# VM-MCU_v4_5.net
KiCad netlist of a schematic drawn in EAGLE
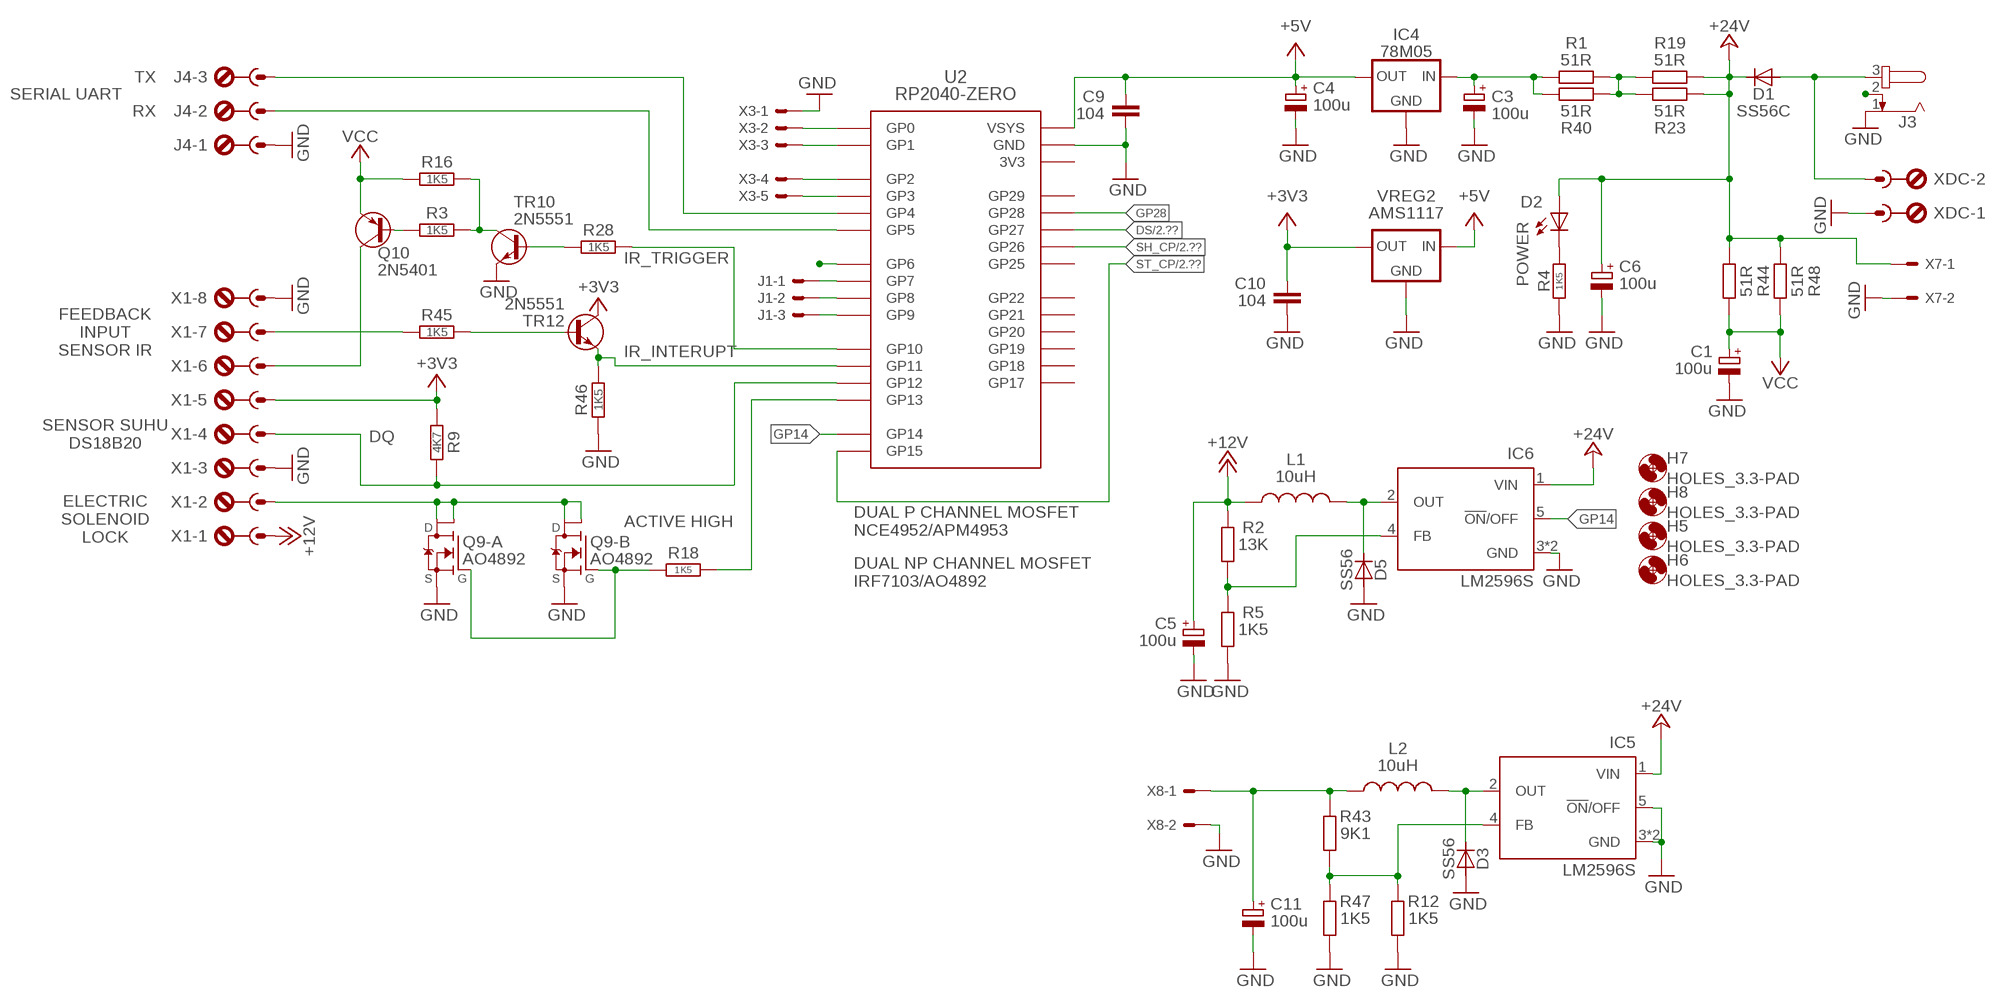
[diagram p0: schematic, sheet 1]
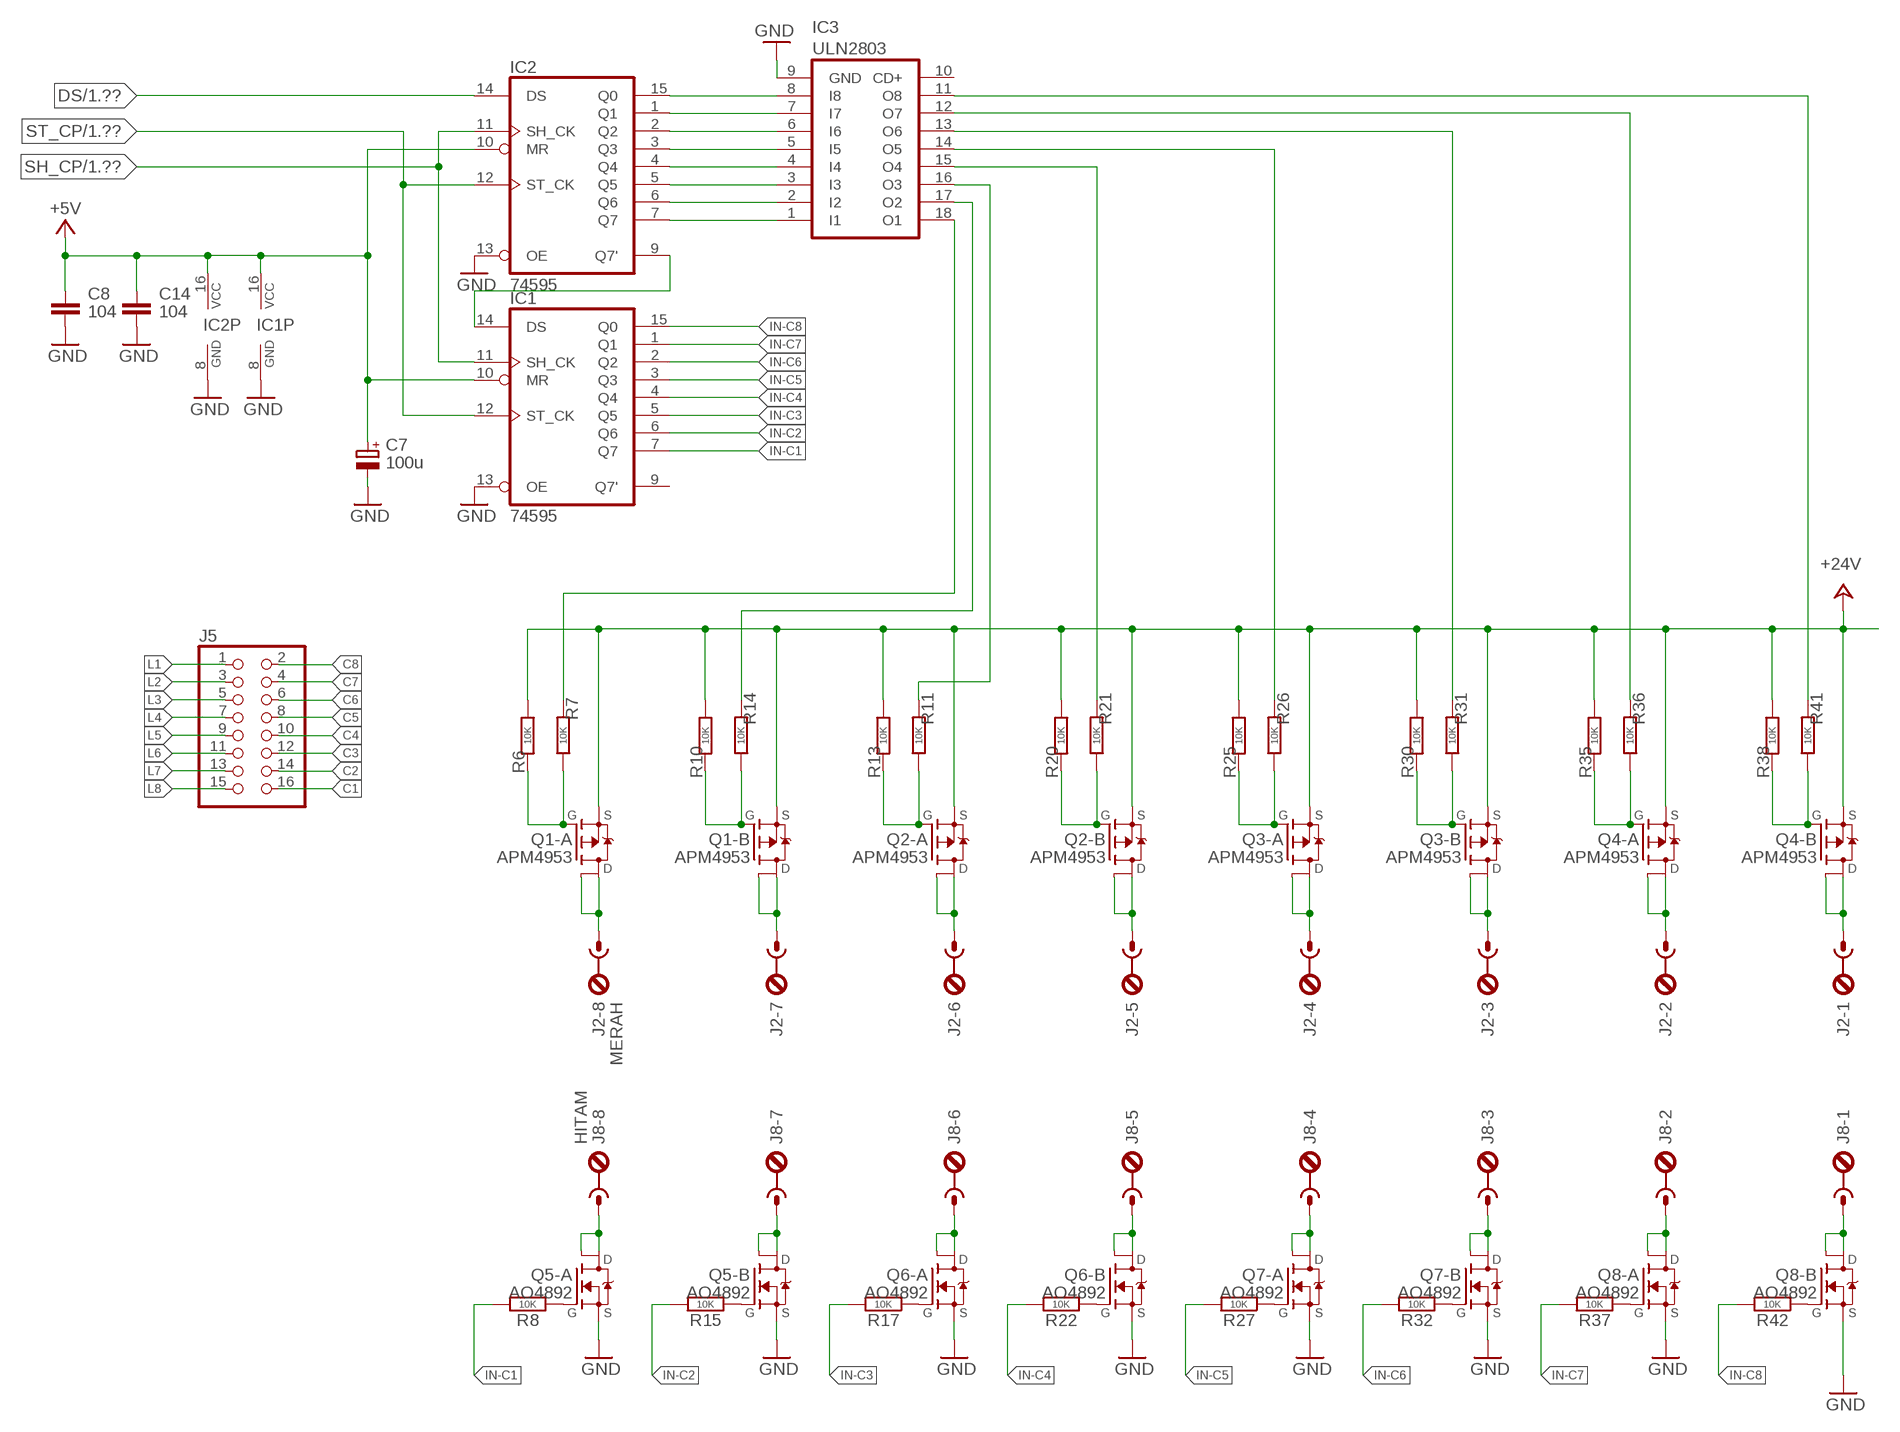
[diagram p1: schematic, sheet 2]

(export (version "E")
  (design (tool "Eeschema 10.0.6"))
  (components
    (comp (ref "C7")
      (value "100u")
      (footprint "eagle-import:UD-6,3X7,7_NICHICON")
      (libsource (lib "eagle-import") (part "ELCO_UD-6,3X7,7"))
    )
    (comp (ref "C8")
      (value "104")
      (footprint "eagle-import:C1206")
      (libsource (lib "eagle-import") (part "CAP_SMD-C1206"))
    )
    (comp (ref "C14")
      (value "104")
      (footprint "eagle-import:C1206")
      (libsource (lib "eagle-import") (part "CAP_SMD-C1206"))
    )
    (comp (ref "IC1")
      (value "74595")
      (footprint "eagle-import:SO16")
      (libsource (lib "eagle-import") (part "74595"))
    )
    (comp (ref "IC2")
      (value "74595")
      (footprint "eagle-import:SO16")
      (libsource (lib "eagle-import") (part "74595"))
    )
    (comp (ref "IC3")
      (value "ULN2803")
      (footprint "eagle-import:SO18W")
      (libsource (lib "eagle-import") (part "ULN2805ASO18"))
    )
    (comp (ref "J2")
      (value "MERAH")
      (footprint "eagle-import:KF2EDG-3.81_8P")
      (libsource (lib "eagle-import") (part "TBLOCK-8P_KF2EDG-3.81"))
    )
    (comp (ref "J5")
      (value "PINHEAD_2X8SMT")
      (footprint "eagle-import:PINHEAD-SMT_2X08")
      (libsource (lib "eagle-import") (part "PINHEAD_2X8SMT"))
    )
    (comp (ref "J8")
      (value "HITAM")
      (footprint "eagle-import:KF2EDG-3.81_8P")
      (libsource (lib "eagle-import") (part "TBLOCK-8P_KF2EDG-3.81"))
    )
    (comp (ref "Q1")
      (value "APM4953")
      (footprint "eagle-import:SO-8")
      (libsource (lib "eagle-import") (part "DUALFET-P_P+PNCE4953"))
    )
    (comp (ref "Q2")
      (value "APM4953")
      (footprint "eagle-import:SO-8")
      (libsource (lib "eagle-import") (part "DUALFET-P_P+PNCE4953"))
    )
    (comp (ref "Q3")
      (value "APM4953")
      (footprint "eagle-import:SO-8")
      (libsource (lib "eagle-import") (part "DUALFET-P_P+PNCE4953"))
    )
    (comp (ref "Q4")
      (value "APM4953")
      (footprint "eagle-import:SO-8")
      (libsource (lib "eagle-import") (part "DUALFET-P_P+PNCE4953"))
    )
    (comp (ref "Q5")
      (value "AO4892")
      (footprint "eagle-import:SO-8")
      (libsource (lib "eagle-import") (part "DUALFET-N_N+NAO4892"))
    )
    (comp (ref "Q6")
      (value "AO4892")
      (footprint "eagle-import:SO-8")
      (libsource (lib "eagle-import") (part "DUALFET-N_N+NAO4892"))
    )
    (comp (ref "Q7")
      (value "AO4892")
      (footprint "eagle-import:SO-8")
      (libsource (lib "eagle-import") (part "DUALFET-N_N+NAO4892"))
    )
    (comp (ref "Q8")
      (value "AO4892")
      (footprint "eagle-import:SO-8")
      (libsource (lib "eagle-import") (part "DUALFET-N_N+NAO4892"))
    )
    (comp (ref "R6")
      (value "10K")
      (footprint "eagle-import:R1206")
      (libsource (lib "eagle-import") (part "RESISTOR_1206"))
    )
    (comp (ref "R7")
      (value "10K")
      (footprint "eagle-import:R1206")
      (libsource (lib "eagle-import") (part "RESISTOR_1206"))
    )
    (comp (ref "R8")
      (value "10K")
      (footprint "eagle-import:R1206")
      (libsource (lib "eagle-import") (part "RESISTOR_1206"))
    )
    (comp (ref "R10")
      (value "10K")
      (footprint "eagle-import:R1206")
      (libsource (lib "eagle-import") (part "RESISTOR_1206"))
    )
    (comp (ref "R11")
      (value "10K")
      (footprint "eagle-import:R1206")
      (libsource (lib "eagle-import") (part "RESISTOR_1206"))
    )
    (comp (ref "R13")
      (value "10K")
      (footprint "eagle-import:R1206")
      (libsource (lib "eagle-import") (part "RESISTOR_1206"))
    )
    (comp (ref "R14")
      (value "10K")
      (footprint "eagle-import:R1206")
      (libsource (lib "eagle-import") (part "RESISTOR_1206"))
    )
    (comp (ref "R15")
      (value "10K")
      (footprint "eagle-import:R1206")
      (libsource (lib "eagle-import") (part "RESISTOR_1206"))
    )
    (comp (ref "R17")
      (value "10K")
      (footprint "eagle-import:R1206")
      (libsource (lib "eagle-import") (part "RESISTOR_1206"))
    )
    (comp (ref "R20")
      (value "10K")
      (footprint "eagle-import:R1206")
      (libsource (lib "eagle-import") (part "RESISTOR_1206"))
    )
    (comp (ref "R21")
      (value "10K")
      (footprint "eagle-import:R1206")
      (libsource (lib "eagle-import") (part "RESISTOR_1206"))
    )
    (comp (ref "R22")
      (value "10K")
      (footprint "eagle-import:R1206")
      (libsource (lib "eagle-import") (part "RESISTOR_1206"))
    )
    (comp (ref "R25")
      (value "10K")
      (footprint "eagle-import:R1206")
      (libsource (lib "eagle-import") (part "RESISTOR_1206"))
    )
    (comp (ref "R26")
      (value "10K")
      (footprint "eagle-import:R1206")
      (libsource (lib "eagle-import") (part "RESISTOR_1206"))
    )
    (comp (ref "R27")
      (value "10K")
      (footprint "eagle-import:R1206")
      (libsource (lib "eagle-import") (part "RESISTOR_1206"))
    )
    (comp (ref "R30")
      (value "10K")
      (footprint "eagle-import:R1206")
      (libsource (lib "eagle-import") (part "RESISTOR_1206"))
    )
    (comp (ref "R31")
      (value "10K")
      (footprint "eagle-import:R1206")
      (libsource (lib "eagle-import") (part "RESISTOR_1206"))
    )
    (comp (ref "R32")
      (value "10K")
      (footprint "eagle-import:R1206")
      (libsource (lib "eagle-import") (part "RESISTOR_1206"))
    )
    (comp (ref "R35")
      (value "10K")
      (footprint "eagle-import:R1206")
      (libsource (lib "eagle-import") (part "RESISTOR_1206"))
    )
    (comp (ref "R36")
      (value "10K")
      (footprint "eagle-import:R1206")
      (libsource (lib "eagle-import") (part "RESISTOR_1206"))
    )
    (comp (ref "R37")
      (value "10K")
      (footprint "eagle-import:R1206")
      (libsource (lib "eagle-import") (part "RESISTOR_1206"))
    )
    (comp (ref "R38")
      (value "10K")
      (footprint "eagle-import:R1206")
      (libsource (lib "eagle-import") (part "RESISTOR_1206"))
    )
    (comp (ref "R41")
      (value "10K")
      (footprint "eagle-import:R1206")
      (libsource (lib "eagle-import") (part "RESISTOR_1206"))
    )
    (comp (ref "R42")
      (value "10K")
      (footprint "eagle-import:R1206")
      (libsource (lib "eagle-import") (part "RESISTOR_1206"))
    )
    (comp (ref "C1")
      (value "100u")
      (footprint "eagle-import:UD-6,3X7,7_NICHICON")
      (libsource (lib "eagle-import") (part "ELCO_UD-6,3X7,7"))
    )
    (comp (ref "C3")
      (value "100u")
      (footprint "eagle-import:UD-6,3X7,7_NICHICON")
      (libsource (lib "eagle-import") (part "ELCO_UD-6,3X7,7"))
    )
    (comp (ref "C4")
      (value "100u")
      (footprint "eagle-import:UD-6,3X7,7_NICHICON")
      (libsource (lib "eagle-import") (part "ELCO_UD-6,3X7,7"))
    )
    (comp (ref "C5")
      (value "100u")
      (footprint "eagle-import:UD-6,3X7,7_NICHICON")
      (libsource (lib "eagle-import") (part "ELCO_UD-6,3X7,7"))
    )
    (comp (ref "C6")
      (value "100u")
      (footprint "eagle-import:UD-6,3X7,7_NICHICON")
      (libsource (lib "eagle-import") (part "ELCO_UD-6,3X7,7"))
    )
    (comp (ref "C9")
      (value "104")
      (footprint "eagle-import:C1206")
      (libsource (lib "eagle-import") (part "CAP_SMD-C1206"))
    )
    (comp (ref "C10")
      (value "104")
      (footprint "eagle-import:C1206")
      (libsource (lib "eagle-import") (part "CAP_SMD-C1206"))
    )
    (comp (ref "C11")
      (value "100u")
      (footprint "eagle-import:UD-6,3X7,7_NICHICON")
      (libsource (lib "eagle-import") (part "ELCO_UD-6,3X7,7"))
    )
    (comp (ref "D1")
      (value "SS56C")
      (footprint "eagle-import:DO214AB")
      (libsource (lib "eagle-import") (part "DIODE_DO214AB-SMC"))
    )
    (comp (ref "D2")
      (value "POWER")
      (footprint "eagle-import:LED2835")
      (libsource (lib "eagle-import") (part "LED2835"))
    )
    (comp (ref "D3")
      (value "SS56")
      (footprint "eagle-import:DO214AC")
      (libsource (lib "eagle-import") (part "DIODE_DO214AC"))
    )
    (comp (ref "D5")
      (value "SS56")
      (footprint "eagle-import:DO214AC")
      (libsource (lib "eagle-import") (part "DIODE_DO214AC"))
    )
    (comp (ref "H5")
      (value "HOLES_3.3-PAD")
      (footprint "eagle-import:3,3-PAD")
      (libsource (lib "eagle-import") (part "HOLES_3.3-PAD"))
    )
    (comp (ref "H6")
      (value "HOLES_3.3-PAD")
      (footprint "eagle-import:3,3-PAD")
      (libsource (lib "eagle-import") (part "HOLES_3.3-PAD"))
    )
    (comp (ref "H7")
      (value "HOLES_3.3-PAD")
      (footprint "eagle-import:3,3-PAD")
      (libsource (lib "eagle-import") (part "HOLES_3.3-PAD"))
    )
    (comp (ref "H8")
      (value "HOLES_3.3-PAD")
      (footprint "eagle-import:3,3-PAD")
      (libsource (lib "eagle-import") (part "HOLES_3.3-PAD"))
    )
    (comp (ref "IC4")
      (value "78M05")
      (footprint "eagle-import:TO252")
      (libsource (lib "eagle-import") (part "78XXX_TO252"))
    )
    (comp (ref "IC5")
      (value "LM2596S")
      (footprint "eagle-import:TO263-5")
      (fields (field (name "MF") "NATIONAL SEMICONDUCTOR") (field (name "MPN") "LM2596S-ADJ/NOPB"))
      (libsource (lib "eagle-import") (part "LM2596S"))
    )
    (comp (ref "IC6")
      (value "LM2596S")
      (footprint "eagle-import:TO263-5")
      (fields (field (name "MF") "NATIONAL SEMICONDUCTOR") (field (name "MPN") "LM2596S-ADJ/NOPB"))
      (libsource (lib "eagle-import") (part "LM2596S"))
    )
    (comp (ref "J1")
      (value "SOKET-3P_JST-XH-2.54")
      (footprint "eagle-import:3P-JST-XH")
      (libsource (lib "eagle-import") (part "SOKET-3P_JST-XH-2.54"))
    )
    (comp (ref "J3")
      (value "JACK-DC_5.5X2.5MM")
      (footprint "eagle-import:DC-5.5X2.5")
      (libsource (lib "eagle-import") (part "JACK-DC_5.5X2.5MM"))
    )
    (comp (ref "J4")
      (value "TBLOCK-3P_KF2EDG-3.81")
      (footprint "eagle-import:KF2EDG-3.81_3P")
      (libsource (lib "eagle-import") (part "TBLOCK-3P_KF2EDG-3.81"))
    )
    (comp (ref "L1")
      (value "10uH")
      (footprint "eagle-import:CDRH127_LD")
      (libsource (lib "eagle-import") (part "INDUKTORSMD"))
    )
    (comp (ref "L2")
      (value "10uH")
      (footprint "eagle-import:CDRH127_LD")
      (libsource (lib "eagle-import") (part "INDUKTORSMD"))
    )
    (comp (ref "Q9")
      (value "AO4892")
      (footprint "eagle-import:SO-8")
      (libsource (lib "eagle-import") (part "DUALFET-N_N+NAO4892"))
    )
    (comp (ref "Q10")
      (value "2N5401")
      (footprint "eagle-import:TO92-EBC")
      (libsource (lib "eagle-import") (part "BJT-PNP_TO92-EBC"))
    )
    (comp (ref "R1")
      (value "51R")
      (footprint "eagle-import:R2512")
      (libsource (lib "eagle-import") (part "RESISTOR_2512"))
    )
    (comp (ref "R2")
      (value "13K")
      (footprint "eagle-import:R1206")
      (libsource (lib "eagle-import") (part "VM-MCU_RESISTOR_1206"))
    )
    (comp (ref "R3")
      (value "1K5")
      (footprint "eagle-import:R1206")
      (libsource (lib "eagle-import") (part "VM-MCU_RESISTOR_1206"))
    )
    (comp (ref "R4")
      (value "1K5")
      (footprint "eagle-import:R1206")
      (libsource (lib "eagle-import") (part "RESISTOR_1206"))
    )
    (comp (ref "R5")
      (value "1K5")
      (footprint "eagle-import:R1206")
      (libsource (lib "eagle-import") (part "VM-MCU_RESISTOR_1206"))
    )
    (comp (ref "R9")
      (value "4K7")
      (footprint "eagle-import:R1206")
      (libsource (lib "eagle-import") (part "VM-MCU_RESISTOR_1206"))
    )
    (comp (ref "R12")
      (value "1K5")
      (footprint "eagle-import:R1206")
      (libsource (lib "eagle-import") (part "VM-MCU_RESISTOR_1206"))
    )
    (comp (ref "R16")
      (value "1K5")
      (footprint "eagle-import:R1206")
      (libsource (lib "eagle-import") (part "VM-MCU_RESISTOR_1206"))
    )
    (comp (ref "R18")
      (value "1K5")
      (footprint "eagle-import:R1206")
      (libsource (lib "eagle-import") (part "VM-MCU_RESISTOR_1206"))
    )
    (comp (ref "R19")
      (value "51R")
      (footprint "eagle-import:R2512")
      (libsource (lib "eagle-import") (part "RESISTOR_2512"))
    )
    (comp (ref "R23")
      (value "51R")
      (footprint "eagle-import:R2512")
      (libsource (lib "eagle-import") (part "RESISTOR_2512"))
    )
    (comp (ref "R28")
      (value "1K5")
      (footprint "eagle-import:R1206")
      (libsource (lib "eagle-import") (part "VM-MCU_RESISTOR_1206"))
    )
    (comp (ref "R40")
      (value "51R")
      (footprint "eagle-import:R2512")
      (libsource (lib "eagle-import") (part "RESISTOR_2512"))
    )
    (comp (ref "R43")
      (value "9K1")
      (footprint "eagle-import:R1206")
      (libsource (lib "eagle-import") (part "VM-MCU_RESISTOR_1206"))
    )
    (comp (ref "R44")
      (value "51R")
      (footprint "eagle-import:R2512")
      (libsource (lib "eagle-import") (part "RESISTOR_2512"))
    )
    (comp (ref "R45")
      (value "1K5")
      (footprint "eagle-import:R1206")
      (libsource (lib "eagle-import") (part "RESISTOR_1206"))
    )
    (comp (ref "R46")
      (value "1K5")
      (footprint "eagle-import:R1206")
      (libsource (lib "eagle-import") (part "VM-MCU_RESISTOR_1206"))
    )
    (comp (ref "R47")
      (value "1K5")
      (footprint "eagle-import:R1206")
      (libsource (lib "eagle-import") (part "VM-MCU_RESISTOR_1206"))
    )
    (comp (ref "R48")
      (value "51R")
      (footprint "eagle-import:R2512")
      (libsource (lib "eagle-import") (part "RESISTOR_2512"))
    )
    (comp (ref "TR10")
      (value "2N5551")
      (footprint "eagle-import:TO92-EBC")
      (libsource (lib "eagle-import") (part "BJT-NPN_TO92-EBC"))
    )
    (comp (ref "TR12")
      (value "2N5551")
      (footprint "eagle-import:TO92-EBC")
      (libsource (lib "eagle-import") (part "BJT-NPN_TO92-EBC"))
    )
    (comp (ref "U2")
      (value "RP2040-ZERO")
      (footprint "eagle-import:PICO-ZERO-SMT-C")
      (libsource (lib "eagle-import") (part "RASPBERRY-PICO-ZERO-SMT_TYPE-C"))
    )
    (comp (ref "VREG2")
      (value "AMS1117")
      (footprint "eagle-import:SOT223")
      (libsource (lib "eagle-import") (part "78XXX_SOT223"))
    )
    (comp (ref "X1")
      (value "TBLOCK-8P_KF2EDG-3.81")
      (footprint "eagle-import:KF2EDG-3.81_8P")
      (libsource (lib "eagle-import") (part "TBLOCK-8P_KF2EDG-3.81"))
    )
    (comp (ref "X3")
      (value "SOKET-5P_JST-XH-2.54")
      (footprint "eagle-import:5P-JST-XH")
      (libsource (lib "eagle-import") (part "SOKET-5P_JST-XH-2.54"))
    )
    (comp (ref "X7")
      (value "SOKET-2P_JST-XH-2.54")
      (footprint "eagle-import:2P-JST-XH")
      (libsource (lib "eagle-import") (part "SOKET-2P_JST-XH-2.54"))
    )
    (comp (ref "X8")
      (value "SOKET-2P_JST-XH-2.54")
      (footprint "eagle-import:2P-JST-XH")
      (libsource (lib "eagle-import") (part "SOKET-2P_JST-XH-2.54"))
    )
    (comp (ref "XDC")
      (value "TBLOCK-2P_5.08MM")
      (footprint "eagle-import:KF128-5_2P")
      (libsource (lib "eagle-import") (part "TBLOCK-2P_5.08MM"))
    )
  )
  (nets
    (net (code "1") (name "+3V3") (class "Default")
      (node (ref "C10") (pin "1") (pinfunction "1_1") (pintype "passive"))
      (node (ref "R9") (pin "1") (pinfunction "1_1") (pintype "passive"))
      (node (ref "TR12") (pin "C") (pinfunction "C_C") (pintype "passive"))
      (node (ref "VREG2") (pin "4") (pinfunction "OUT_4") (pintype "passive"))
      (node (ref "X1") (pin "5") (pinfunction "1_5") (pintype "passive"))
    )
    (net (code "2") (name "+5V") (class "Default")
      (node (ref "C14") (pin "1") (pinfunction "1_1") (pintype "passive"))
      (node (ref "C4") (pin "+") (pinfunction "+_+") (pintype "passive"))
      (node (ref "C7") (pin "+") (pinfunction "+_+") (pintype "passive"))
      (node (ref "C8") (pin "1") (pinfunction "1_1") (pintype "passive"))
      (node (ref "C9") (pin "1") (pinfunction "1_1") (pintype "passive"))
      (node (ref "IC1") (pin "10") (pinfunction "MR_10") (pintype "input"))
      (node (ref "IC1") (pin "16") (pinfunction "VCC_16") (pintype "power_in"))
      (node (ref "IC2") (pin "10") (pinfunction "MR_10") (pintype "input"))
      (node (ref "IC2") (pin "16") (pinfunction "VCC_16") (pintype "power_in"))
      (node (ref "IC4") (pin "2") (pinfunction "OUT_2") (pintype "passive"))
      (node (ref "U2") (pin "5V") (pinfunction "VSYS_5V") (pintype "power_in"))
      (node (ref "VREG2") (pin "3") (pinfunction "IN_3") (pintype "input"))
    )
    (net (code "3") (name "+12V") (class "Default")
      (node (ref "C5") (pin "+") (pinfunction "+_+") (pintype "passive"))
      (node (ref "L1") (pin "1") (pinfunction "1_1") (pintype "passive"))
      (node (ref "R2") (pin "1") (pinfunction "1_1") (pintype "passive"))
      (node (ref "X1") (pin "1") (pinfunction "1_1") (pintype "passive"))
    )
    (net (code "4") (name "+24V") (class "Default")
      (node (ref "C6") (pin "+") (pinfunction "+_+") (pintype "passive"))
      (node (ref "D1") (pin "C") (pinfunction "C_C") (pintype "passive"))
      (node (ref "D2") (pin "A") (pinfunction "A_A") (pintype "passive"))
      (node (ref "IC5") (pin "1") (pinfunction "VIN_1") (pintype "input"))
      (node (ref "IC6") (pin "1") (pinfunction "VIN_1") (pintype "input"))
      (node (ref "Q1") (pin "1") (pinfunction "S_1") (pintype "passive"))
      (node (ref "Q1") (pin "3") (pinfunction "S_3") (pintype "passive"))
      (node (ref "Q2") (pin "1") (pinfunction "S_1") (pintype "passive"))
      (node (ref "Q2") (pin "3") (pinfunction "S_3") (pintype "passive"))
      (node (ref "Q3") (pin "1") (pinfunction "S_1") (pintype "passive"))
      (node (ref "Q3") (pin "3") (pinfunction "S_3") (pintype "passive"))
      (node (ref "Q4") (pin "1") (pinfunction "S_1") (pintype "passive"))
      (node (ref "Q4") (pin "3") (pinfunction "S_3") (pintype "passive"))
      (node (ref "R10") (pin "1") (pinfunction "1_1") (pintype "passive"))
      (node (ref "R13") (pin "1") (pinfunction "1_1") (pintype "passive"))
      (node (ref "R19") (pin "2") (pinfunction "2_2") (pintype "passive"))
      (node (ref "R20") (pin "1") (pinfunction "1_1") (pintype "passive"))
      (node (ref "R23") (pin "1") (pinfunction "1_1") (pintype "passive"))
      (node (ref "R25") (pin "1") (pinfunction "1_1") (pintype "passive"))
      (node (ref "R30") (pin "1") (pinfunction "1_1") (pintype "passive"))
      (node (ref "R35") (pin "1") (pinfunction "1_1") (pintype "passive"))
      (node (ref "R38") (pin "1") (pinfunction "1_1") (pintype "passive"))
      (node (ref "R44") (pin "1") (pinfunction "1_1") (pintype "passive"))
      (node (ref "R48") (pin "1") (pinfunction "1_1") (pintype "passive"))
      (node (ref "R6") (pin "1") (pinfunction "1_1") (pintype "passive"))
      (node (ref "X7") (pin "1") (pinfunction "S_1") (pintype "passive"))
    )
    (net (code "5") (name "3V3") (class "Default")
      (node (ref "U2") (pin "3V3") (pinfunction "3V3_3V3") (pintype "power_in"))
    )
    (net (code "6") (name "C1") (class "Default")
      (node (ref "J5") (pin "16") (pinfunction "16_16") (pintype "passive"))
      (node (ref "J8") (pin "8") (pinfunction "1_8") (pintype "passive"))
      (node (ref "Q5") (pin "7") (pinfunction "D2_7") (pintype "passive"))
      (node (ref "Q5") (pin "8") (pinfunction "D1_8") (pintype "passive"))
    )
    (net (code "7") (name "C2") (class "Default")
      (node (ref "J5") (pin "14") (pinfunction "14_14") (pintype "passive"))
      (node (ref "J8") (pin "7") (pinfunction "1_7") (pintype "passive"))
      (node (ref "Q5") (pin "5") (pinfunction "D1_5") (pintype "passive"))
      (node (ref "Q5") (pin "6") (pinfunction "D2_6") (pintype "passive"))
    )
    (net (code "8") (name "C3") (class "Default")
      (node (ref "J5") (pin "12") (pinfunction "12_12") (pintype "passive"))
      (node (ref "J8") (pin "6") (pinfunction "1_6") (pintype "passive"))
      (node (ref "Q6") (pin "7") (pinfunction "D2_7") (pintype "passive"))
      (node (ref "Q6") (pin "8") (pinfunction "D1_8") (pintype "passive"))
    )
    (net (code "9") (name "C4") (class "Default")
      (node (ref "J5") (pin "10") (pinfunction "10_10") (pintype "passive"))
      (node (ref "J8") (pin "5") (pinfunction "1_5") (pintype "passive"))
      (node (ref "Q6") (pin "5") (pinfunction "D1_5") (pintype "passive"))
      (node (ref "Q6") (pin "6") (pinfunction "D2_6") (pintype "passive"))
    )
    (net (code "10") (name "C5") (class "Default")
      (node (ref "J5") (pin "8") (pinfunction "8_8") (pintype "passive"))
      (node (ref "J8") (pin "4") (pinfunction "1_4") (pintype "passive"))
      (node (ref "Q7") (pin "7") (pinfunction "D2_7") (pintype "passive"))
      (node (ref "Q7") (pin "8") (pinfunction "D1_8") (pintype "passive"))
    )
    (net (code "11") (name "C6") (class "Default")
      (node (ref "J5") (pin "6") (pinfunction "6_6") (pintype "passive"))
      (node (ref "J8") (pin "3") (pinfunction "1_3") (pintype "passive"))
      (node (ref "Q7") (pin "5") (pinfunction "D1_5") (pintype "passive"))
      (node (ref "Q7") (pin "6") (pinfunction "D2_6") (pintype "passive"))
    )
    (net (code "12") (name "C7") (class "Default")
      (node (ref "J5") (pin "4") (pinfunction "4_4") (pintype "passive"))
      (node (ref "J8") (pin "2") (pinfunction "1_2") (pintype "passive"))
      (node (ref "Q8") (pin "7") (pinfunction "D2_7") (pintype "passive"))
      (node (ref "Q8") (pin "8") (pinfunction "D1_8") (pintype "passive"))
    )
    (net (code "13") (name "C8") (class "Default")
      (node (ref "J5") (pin "2") (pinfunction "2_2") (pintype "passive"))
      (node (ref "J8") (pin "1") (pinfunction "1_1") (pintype "passive"))
      (node (ref "Q8") (pin "5") (pinfunction "D1_5") (pintype "passive"))
      (node (ref "Q8") (pin "6") (pinfunction "D2_6") (pintype "passive"))
    )
    (net (code "14") (name "DS") (class "Default")
      (node (ref "IC2") (pin "14") (pinfunction "DS_14") (pintype "input"))
      (node (ref "U2") (pin "P27") (pinfunction "GP27_P27") (pintype "bidirectional"))
    )
    (net (code "15") (name "GND") (class "Default")
      (node (ref "C1") (pin "-") (pinfunction "-_-") (pintype "passive"))
      (node (ref "C10") (pin "2") (pinfunction "2_2") (pintype "passive"))
      (node (ref "C11") (pin "-") (pinfunction "-_-") (pintype "passive"))
      (node (ref "C14") (pin "2") (pinfunction "2_2") (pintype "passive"))
      (node (ref "C3") (pin "-") (pinfunction "-_-") (pintype "passive"))
      (node (ref "C4") (pin "-") (pinfunction "-_-") (pintype "passive"))
      (node (ref "C5") (pin "-") (pinfunction "-_-") (pintype "passive"))
      (node (ref "C6") (pin "-") (pinfunction "-_-") (pintype "passive"))
      (node (ref "C7") (pin "-") (pinfunction "-_-") (pintype "passive"))
      (node (ref "C8") (pin "2") (pinfunction "2_2") (pintype "passive"))
      (node (ref "C9") (pin "2") (pinfunction "2_2") (pintype "passive"))
      (node (ref "D3") (pin "A") (pinfunction "A_A") (pintype "passive"))
      (node (ref "D5") (pin "A") (pinfunction "A_A") (pintype "passive"))
      (node (ref "IC1") (pin "13") (pinfunction "OE_13") (pintype "input"))
      (node (ref "IC1") (pin "8") (pinfunction "GND_8") (pintype "power_in"))
      (node (ref "IC2") (pin "13") (pinfunction "OE_13") (pintype "input"))
      (node (ref "IC2") (pin "8") (pinfunction "GND_8") (pintype "power_in"))
      (node (ref "IC3") (pin "9") (pinfunction "GND_9") (pintype "power_in"))
      (node (ref "IC4") (pin "3") (pinfunction "GND_3") (pintype "input"))
      (node (ref "IC5") (pin "3") (pinfunction "GND_3") (pintype "power_in"))
      (node (ref "IC5") (pin "5") (pinfunction "~{ON}/OFF_5") (pintype "input"))
      (node (ref "IC5") (pin "6") (pinfunction "GND_6") (pintype "power_in"))
      (node (ref "IC6") (pin "3") (pinfunction "GND_3") (pintype "power_in"))
      (node (ref "IC6") (pin "6") (pinfunction "GND_6") (pintype "power_in"))
      (node (ref "J3") (pin "1") (pinfunction "1_1") (pintype "passive"))
      (node (ref "J4") (pin "1") (pinfunction "1_1") (pintype "passive"))
      (node (ref "Q5") (pin "1") (pinfunction "S_1") (pintype "passive"))
      (node (ref "Q5") (pin "3") (pinfunction "S_3") (pintype "passive"))
      (node (ref "Q6") (pin "1") (pinfunction "S_1") (pintype "passive"))
      (node (ref "Q6") (pin "3") (pinfunction "S_3") (pintype "passive"))
      (node (ref "Q7") (pin "1") (pinfunction "S_1") (pintype "passive"))
      (node (ref "Q7") (pin "3") (pinfunction "S_3") (pintype "passive"))
      (node (ref "Q8") (pin "1") (pinfunction "S_1") (pintype "passive"))
      (node (ref "Q8") (pin "3") (pinfunction "S_3") (pintype "passive"))
      (node (ref "Q9") (pin "1") (pinfunction "S_1") (pintype "passive"))
      (node (ref "Q9") (pin "3") (pinfunction "S_3") (pintype "passive"))
      (node (ref "R12") (pin "2") (pinfunction "2_2") (pintype "passive"))
      (node (ref "R4") (pin "1") (pinfunction "1_1") (pintype "passive"))
      (node (ref "R46") (pin "1") (pinfunction "1_1") (pintype "passive"))
      (node (ref "R47") (pin "2") (pinfunction "2_2") (pintype "passive"))
      (node (ref "R5") (pin "2") (pinfunction "2_2") (pintype "passive"))
      (node (ref "TR10") (pin "E") (pinfunction "E_E") (pintype "passive"))
      (node (ref "U2") (pin "G") (pinfunction "GND_G") (pintype "power_in"))
      (node (ref "VREG2") (pin "1") (pinfunction "GND_1") (pintype "input"))
      (node (ref "X1") (pin "3") (pinfunction "1_3") (pintype "passive"))
      (node (ref "X1") (pin "8") (pinfunction "1_8") (pintype "passive"))
      (node (ref "X3") (pin "1") (pinfunction "S_1") (pintype "passive"))
      (node (ref "X7") (pin "2") (pinfunction "S_2") (pintype "passive"))
      (node (ref "X8") (pin "2") (pinfunction "S_2") (pintype "passive"))
      (node (ref "XDC") (pin "1") (pinfunction "1_1") (pintype "passive"))
    )
    (net (code "16") (name "GP14") (class "Default")
      (node (ref "IC6") (pin "5") (pinfunction "~{ON}/OFF_5") (pintype "input"))
      (node (ref "U2") (pin "P14") (pinfunction "GP14_P14") (pintype "bidirectional"))
    )
    (net (code "17") (name "GP28") (class "Default")
      (node (ref "U2") (pin "P28") (pinfunction "GP28_P28") (pintype "bidirectional"))
    )
    (net (code "18") (name "IN-C1") (class "Default")
      (node (ref "IC1") (pin "7") (pinfunction "Q7_7") (pintype "tri_state"))
      (node (ref "R8") (pin "2") (pinfunction "2_2") (pintype "passive"))
    )
    (net (code "19") (name "IN-C2") (class "Default")
      (node (ref "IC1") (pin "6") (pinfunction "Q6_6") (pintype "tri_state"))
      (node (ref "R15") (pin "2") (pinfunction "2_2") (pintype "passive"))
    )
    (net (code "20") (name "IN-C3") (class "Default")
      (node (ref "IC1") (pin "5") (pinfunction "Q5_5") (pintype "tri_state"))
      (node (ref "R17") (pin "2") (pinfunction "2_2") (pintype "passive"))
    )
    (net (code "21") (name "IN-C4") (class "Default")
      (node (ref "IC1") (pin "4") (pinfunction "Q4_4") (pintype "tri_state"))
      (node (ref "R22") (pin "2") (pinfunction "2_2") (pintype "passive"))
    )
    (net (code "22") (name "IN-C5") (class "Default")
      (node (ref "IC1") (pin "3") (pinfunction "Q3_3") (pintype "tri_state"))
      (node (ref "R27") (pin "2") (pinfunction "2_2") (pintype "passive"))
    )
    (net (code "23") (name "IN-C6") (class "Default")
      (node (ref "IC1") (pin "2") (pinfunction "Q2_2") (pintype "tri_state"))
      (node (ref "R32") (pin "2") (pinfunction "2_2") (pintype "passive"))
    )
    (net (code "24") (name "IN-C7") (class "Default")
      (node (ref "IC1") (pin "1") (pinfunction "Q1_1") (pintype "tri_state"))
      (node (ref "R37") (pin "2") (pinfunction "2_2") (pintype "passive"))
    )
    (net (code "25") (name "IN-C8") (class "Default")
      (node (ref "IC1") (pin "15") (pinfunction "Q0_15") (pintype "tri_state"))
      (node (ref "R42") (pin "2") (pinfunction "2_2") (pintype "passive"))
    )
    (net (code "26") (name "L1") (class "Default")
      (node (ref "J2") (pin "8") (pinfunction "1_8") (pintype "passive"))
      (node (ref "J5") (pin "1") (pinfunction "1_1") (pintype "passive"))
      (node (ref "Q1") (pin "7") (pinfunction "D2_7") (pintype "passive"))
      (node (ref "Q1") (pin "8") (pinfunction "D1_8") (pintype "passive"))
    )
    (net (code "27") (name "L2") (class "Default")
      (node (ref "J2") (pin "7") (pinfunction "1_7") (pintype "passive"))
      (node (ref "J5") (pin "3") (pinfunction "3_3") (pintype "passive"))
      (node (ref "Q1") (pin "5") (pinfunction "D1_5") (pintype "passive"))
      (node (ref "Q1") (pin "6") (pinfunction "D2_6") (pintype "passive"))
    )
    (net (code "28") (name "L3") (class "Default")
      (node (ref "J2") (pin "6") (pinfunction "1_6") (pintype "passive"))
      (node (ref "J5") (pin "5") (pinfunction "5_5") (pintype "passive"))
      (node (ref "Q2") (pin "7") (pinfunction "D2_7") (pintype "passive"))
      (node (ref "Q2") (pin "8") (pinfunction "D1_8") (pintype "passive"))
    )
    (net (code "29") (name "L4") (class "Default")
      (node (ref "J2") (pin "5") (pinfunction "1_5") (pintype "passive"))
      (node (ref "J5") (pin "7") (pinfunction "7_7") (pintype "passive"))
      (node (ref "Q2") (pin "5") (pinfunction "D1_5") (pintype "passive"))
      (node (ref "Q2") (pin "6") (pinfunction "D2_6") (pintype "passive"))
    )
    (net (code "30") (name "L5") (class "Default")
      (node (ref "J2") (pin "4") (pinfunction "1_4") (pintype "passive"))
      (node (ref "J5") (pin "9") (pinfunction "9_9") (pintype "passive"))
      (node (ref "Q3") (pin "7") (pinfunction "D2_7") (pintype "passive"))
      (node (ref "Q3") (pin "8") (pinfunction "D1_8") (pintype "passive"))
    )
    (net (code "31") (name "L6") (class "Default")
      (node (ref "J2") (pin "3") (pinfunction "1_3") (pintype "passive"))
      (node (ref "J5") (pin "11") (pinfunction "11_11") (pintype "passive"))
      (node (ref "Q3") (pin "5") (pinfunction "D1_5") (pintype "passive"))
      (node (ref "Q3") (pin "6") (pinfunction "D2_6") (pintype "passive"))
    )
    (net (code "32") (name "L7") (class "Default")
      (node (ref "J2") (pin "2") (pinfunction "1_2") (pintype "passive"))
      (node (ref "J5") (pin "13") (pinfunction "13_13") (pintype "passive"))
      (node (ref "Q4") (pin "7") (pinfunction "D2_7") (pintype "passive"))
      (node (ref "Q4") (pin "8") (pinfunction "D1_8") (pintype "passive"))
    )
    (net (code "33") (name "L8") (class "Default")
      (node (ref "J2") (pin "1") (pinfunction "1_1") (pintype "passive"))
      (node (ref "J5") (pin "15") (pinfunction "15_15") (pintype "passive"))
      (node (ref "Q4") (pin "5") (pinfunction "D1_5") (pintype "passive"))
      (node (ref "Q4") (pin "6") (pinfunction "D2_6") (pintype "passive"))
    )
    (net (code "34") (name "Net-(D2-PadC)") (class "Default")
      (node (ref "D2") (pin "C") (pinfunction "C_C") (pintype "passive"))
      (node (ref "R4") (pin "2") (pinfunction "2_2") (pintype "passive"))
    )
    (net (code "35") (name "Net-(IC1A-DS)") (class "Default")
      (node (ref "IC1") (pin "14") (pinfunction "DS_14") (pintype "input"))
      (node (ref "IC2") (pin "9") (pinfunction "Q7'_9") (pintype "tri_state"))
    )
    (net (code "36") (name "Net-(IC2A-Q0)") (class "Default")
      (node (ref "IC2") (pin "15") (pinfunction "Q0_15") (pintype "tri_state"))
      (node (ref "IC3") (pin "8") (pinfunction "I8_8") (pintype "input"))
    )
    (net (code "37") (name "Net-(IC2A-Q1)") (class "Default")
      (node (ref "IC2") (pin "1") (pinfunction "Q1_1") (pintype "tri_state"))
      (node (ref "IC3") (pin "7") (pinfunction "I7_7") (pintype "input"))
    )
    (net (code "38") (name "Net-(IC2A-Q2)") (class "Default")
      (node (ref "IC2") (pin "2") (pinfunction "Q2_2") (pintype "tri_state"))
      (node (ref "IC3") (pin "6") (pinfunction "I6_6") (pintype "input"))
    )
    (net (code "39") (name "Net-(IC2A-Q3)") (class "Default")
      (node (ref "IC2") (pin "3") (pinfunction "Q3_3") (pintype "tri_state"))
      (node (ref "IC3") (pin "5") (pinfunction "I5_5") (pintype "input"))
    )
    (net (code "40") (name "Net-(IC2A-Q4)") (class "Default")
      (node (ref "IC2") (pin "4") (pinfunction "Q4_4") (pintype "tri_state"))
      (node (ref "IC3") (pin "4") (pinfunction "I4_4") (pintype "input"))
    )
    (net (code "41") (name "Net-(IC2A-Q5)") (class "Default")
      (node (ref "IC2") (pin "5") (pinfunction "Q5_5") (pintype "tri_state"))
      (node (ref "IC3") (pin "3") (pinfunction "I3_3") (pintype "input"))
    )
    (net (code "42") (name "Net-(IC2A-Q6)") (class "Default")
      (node (ref "IC2") (pin "6") (pinfunction "Q6_6") (pintype "tri_state"))
      (node (ref "IC3") (pin "2") (pinfunction "I2_2") (pintype "input"))
    )
    (net (code "43") (name "Net-(IC2A-Q7)") (class "Default")
      (node (ref "IC2") (pin "7") (pinfunction "Q7_7") (pintype "tri_state"))
      (node (ref "IC3") (pin "1") (pinfunction "I1_1") (pintype "input"))
    )
    (net (code "44") (name "Net-(IC3-O1)") (class "Default")
      (node (ref "IC3") (pin "18") (pinfunction "O1_18") (pintype "open_collector"))
      (node (ref "R7") (pin "2") (pinfunction "2_2") (pintype "passive"))
    )
    (net (code "45") (name "Net-(IC3-O2)") (class "Default")
      (node (ref "IC3") (pin "17") (pinfunction "O2_17") (pintype "open_collector"))
      (node (ref "R14") (pin "2") (pinfunction "2_2") (pintype "passive"))
    )
    (net (code "46") (name "Net-(IC3-O3)") (class "Default")
      (node (ref "IC3") (pin "16") (pinfunction "O3_16") (pintype "open_collector"))
      (node (ref "R11") (pin "2") (pinfunction "2_2") (pintype "passive"))
    )
    (net (code "47") (name "Net-(IC3-O4)") (class "Default")
      (node (ref "IC3") (pin "15") (pinfunction "O4_15") (pintype "open_collector"))
      (node (ref "R21") (pin "2") (pinfunction "2_2") (pintype "passive"))
    )
    (net (code "48") (name "Net-(IC3-O5)") (class "Default")
      (node (ref "IC3") (pin "14") (pinfunction "O5_14") (pintype "open_collector"))
      (node (ref "R26") (pin "2") (pinfunction "2_2") (pintype "passive"))
    )
    (net (code "49") (name "Net-(IC3-O6)") (class "Default")
      (node (ref "IC3") (pin "13") (pinfunction "O6_13") (pintype "open_collector"))
      (node (ref "R31") (pin "2") (pinfunction "2_2") (pintype "passive"))
    )
    (net (code "50") (name "Net-(IC3-O7)") (class "Default")
      (node (ref "IC3") (pin "12") (pinfunction "O7_12") (pintype "open_collector"))
      (node (ref "R36") (pin "2") (pinfunction "2_2") (pintype "passive"))
    )
    (net (code "51") (name "Net-(IC3-O8)") (class "Default")
      (node (ref "IC3") (pin "11") (pinfunction "O8_11") (pintype "open_collector"))
      (node (ref "R41") (pin "2") (pinfunction "2_2") (pintype "passive"))
    )
    (net (code "52") (name "Net-(IC4-IN)") (class "Default")
      (node (ref "C3") (pin "+") (pinfunction "+_+") (pintype "passive"))
      (node (ref "IC4") (pin "1") (pinfunction "IN_1") (pintype "input"))
      (node (ref "R1") (pin "1") (pinfunction "1_1") (pintype "passive"))
      (node (ref "R40") (pin "2") (pinfunction "2_2") (pintype "passive"))
    )
    (net (code "53") (name "Net-(IC5-FB)") (class "Default")
      (node (ref "IC5") (pin "4") (pinfunction "FB_4") (pintype "input"))
      (node (ref "R12") (pin "1") (pinfunction "1_1") (pintype "passive"))
      (node (ref "R43") (pin "2") (pinfunction "2_2") (pintype "passive"))
      (node (ref "R47") (pin "1") (pinfunction "1_1") (pintype "passive"))
    )
    (net (code "54") (name "Net-(IC5-OUT)") (class "Default")
      (node (ref "D3") (pin "C") (pinfunction "C_C") (pintype "passive"))
      (node (ref "IC5") (pin "2") (pinfunction "OUT_2") (pintype "output"))
      (node (ref "L2") (pin "2") (pinfunction "2_2") (pintype "passive"))
    )
    (net (code "55") (name "Net-(IC6-FB)") (class "Default")
      (node (ref "IC6") (pin "4") (pinfunction "FB_4") (pintype "input"))
      (node (ref "R2") (pin "2") (pinfunction "2_2") (pintype "passive"))
      (node (ref "R5") (pin "1") (pinfunction "1_1") (pintype "passive"))
    )
    (net (code "56") (name "Net-(IC6-OUT)") (class "Default")
      (node (ref "D5") (pin "C") (pinfunction "C_C") (pintype "passive"))
      (node (ref "IC6") (pin "2") (pinfunction "OUT_2") (pintype "output"))
      (node (ref "L1") (pin "2") (pinfunction "2_2") (pintype "passive"))
    )
    (net (code "57") (name "Net-(J1A-S)") (class "Default")
      (node (ref "J1") (pin "1") (pinfunction "S_1") (pintype "passive"))
      (node (ref "U2") (pin "P7") (pinfunction "GP7_P7") (pintype "bidirectional"))
    )
    (net (code "58") (name "Net-(J1B-S)") (class "Default")
      (node (ref "J1") (pin "2") (pinfunction "S_2") (pintype "passive"))
      (node (ref "U2") (pin "P8") (pinfunction "GP8_P8") (pintype "bidirectional"))
    )
    (net (code "59") (name "Net-(J1C-S)") (class "Default")
      (node (ref "J1") (pin "3") (pinfunction "S_3") (pintype "passive"))
      (node (ref "U2") (pin "P9") (pinfunction "GP9_P9") (pintype "bidirectional"))
    )
    (net (code "60") (name "Net-(J4B-1)") (class "Default")
      (node (ref "J4") (pin "2") (pinfunction "1_2") (pintype "passive"))
      (node (ref "U2") (pin "P5") (pinfunction "GP5_P5") (pintype "bidirectional"))
    )
    (net (code "61") (name "Net-(J4C-1)") (class "Default")
      (node (ref "J4") (pin "3") (pinfunction "1_3") (pintype "passive"))
      (node (ref "U2") (pin "P4") (pinfunction "GP4_P4") (pintype "bidirectional"))
    )
    (net (code "62") (name "Net-(Q1A-G)") (class "Default")
      (node (ref "Q1") (pin "2") (pinfunction "G_2") (pintype "passive"))
      (node (ref "R6") (pin "2") (pinfunction "2_2") (pintype "passive"))
      (node (ref "R7") (pin "1") (pinfunction "1_1") (pintype "passive"))
    )
    (net (code "63") (name "Net-(Q1B-G)") (class "Default")
      (node (ref "Q1") (pin "4") (pinfunction "G_4") (pintype "passive"))
      (node (ref "R10") (pin "2") (pinfunction "2_2") (pintype "passive"))
      (node (ref "R14") (pin "1") (pinfunction "1_1") (pintype "passive"))
    )
    (net (code "64") (name "Net-(Q2A-G)") (class "Default")
      (node (ref "Q2") (pin "2") (pinfunction "G_2") (pintype "passive"))
      (node (ref "R11") (pin "1") (pinfunction "1_1") (pintype "passive"))
      (node (ref "R13") (pin "2") (pinfunction "2_2") (pintype "passive"))
    )
    (net (code "65") (name "Net-(Q2B-G)") (class "Default")
      (node (ref "Q2") (pin "4") (pinfunction "G_4") (pintype "passive"))
      (node (ref "R20") (pin "2") (pinfunction "2_2") (pintype "passive"))
      (node (ref "R21") (pin "1") (pinfunction "1_1") (pintype "passive"))
    )
    (net (code "66") (name "Net-(Q3A-G)") (class "Default")
      (node (ref "Q3") (pin "2") (pinfunction "G_2") (pintype "passive"))
      (node (ref "R25") (pin "2") (pinfunction "2_2") (pintype "passive"))
      (node (ref "R26") (pin "1") (pinfunction "1_1") (pintype "passive"))
    )
    (net (code "67") (name "Net-(Q3B-G)") (class "Default")
      (node (ref "Q3") (pin "4") (pinfunction "G_4") (pintype "passive"))
      (node (ref "R30") (pin "2") (pinfunction "2_2") (pintype "passive"))
      (node (ref "R31") (pin "1") (pinfunction "1_1") (pintype "passive"))
    )
    (net (code "68") (name "Net-(Q4A-G)") (class "Default")
      (node (ref "Q4") (pin "2") (pinfunction "G_2") (pintype "passive"))
      (node (ref "R35") (pin "2") (pinfunction "2_2") (pintype "passive"))
      (node (ref "R36") (pin "1") (pinfunction "1_1") (pintype "passive"))
    )
    (net (code "69") (name "Net-(Q4B-G)") (class "Default")
      (node (ref "Q4") (pin "4") (pinfunction "G_4") (pintype "passive"))
      (node (ref "R38") (pin "2") (pinfunction "2_2") (pintype "passive"))
      (node (ref "R41") (pin "1") (pinfunction "1_1") (pintype "passive"))
    )
    (net (code "70") (name "Net-(Q5A-G)") (class "Default")
      (node (ref "Q5") (pin "2") (pinfunction "G_2") (pintype "passive"))
      (node (ref "R8") (pin "1") (pinfunction "1_1") (pintype "passive"))
    )
    (net (code "71") (name "Net-(Q5B-G)") (class "Default")
      (node (ref "Q5") (pin "4") (pinfunction "G_4") (pintype "passive"))
      (node (ref "R15") (pin "1") (pinfunction "1_1") (pintype "passive"))
    )
    (net (code "72") (name "Net-(Q6A-G)") (class "Default")
      (node (ref "Q6") (pin "2") (pinfunction "G_2") (pintype "passive"))
      (node (ref "R17") (pin "1") (pinfunction "1_1") (pintype "passive"))
    )
    (net (code "73") (name "Net-(Q6B-G)") (class "Default")
      (node (ref "Q6") (pin "4") (pinfunction "G_4") (pintype "passive"))
      (node (ref "R22") (pin "1") (pinfunction "1_1") (pintype "passive"))
    )
    (net (code "74") (name "Net-(Q7A-G)") (class "Default")
      (node (ref "Q7") (pin "2") (pinfunction "G_2") (pintype "passive"))
      (node (ref "R27") (pin "1") (pinfunction "1_1") (pintype "passive"))
    )
    (net (code "75") (name "Net-(Q7B-G)") (class "Default")
      (node (ref "Q7") (pin "4") (pinfunction "G_4") (pintype "passive"))
      (node (ref "R32") (pin "1") (pinfunction "1_1") (pintype "passive"))
    )
    (net (code "76") (name "Net-(Q8A-G)") (class "Default")
      (node (ref "Q8") (pin "2") (pinfunction "G_2") (pintype "passive"))
      (node (ref "R37") (pin "1") (pinfunction "1_1") (pintype "passive"))
    )
    (net (code "77") (name "Net-(Q8B-G)") (class "Default")
      (node (ref "Q8") (pin "4") (pinfunction "G_4") (pintype "passive"))
      (node (ref "R42") (pin "1") (pinfunction "1_1") (pintype "passive"))
    )
    (net (code "78") (name "Net-(Q9A-D1)") (class "Default")
      (node (ref "Q9") (pin "5") (pinfunction "D1_5") (pintype "passive"))
      (node (ref "Q9") (pin "6") (pinfunction "D2_6") (pintype "passive"))
      (node (ref "Q9") (pin "7") (pinfunction "D2_7") (pintype "passive"))
      (node (ref "Q9") (pin "8") (pinfunction "D1_8") (pintype "passive"))
      (node (ref "X1") (pin "2") (pinfunction "1_2") (pintype "passive"))
    )
    (net (code "79") (name "Net-(Q9A-G)") (class "Default")
      (node (ref "Q9") (pin "2") (pinfunction "G_2") (pintype "passive"))
      (node (ref "Q9") (pin "4") (pinfunction "G_4") (pintype "passive"))
      (node (ref "R18") (pin "2") (pinfunction "2_2") (pintype "passive"))
    )
    (net (code "80") (name "Net-(Q10-PadB)") (class "Default")
      (node (ref "Q10") (pin "B") (pinfunction "B_B") (pintype "passive"))
      (node (ref "R3") (pin "1") (pinfunction "1_1") (pintype "passive"))
    )
    (net (code "81") (name "Net-(R1-Pad2)") (class "Default")
      (node (ref "R1") (pin "2") (pinfunction "2_2") (pintype "passive"))
      (node (ref "R19") (pin "1") (pinfunction "1_1") (pintype "passive"))
      (node (ref "R23") (pin "2") (pinfunction "2_2") (pintype "passive"))
      (node (ref "R40") (pin "1") (pinfunction "1_1") (pintype "passive"))
    )
    (net (code "82") (name "Net-(R16-Pad2)") (class "Default")
      (node (ref "R16") (pin "2") (pinfunction "2_2") (pintype "passive"))
      (node (ref "R3") (pin "2") (pinfunction "2_2") (pintype "passive"))
      (node (ref "TR10") (pin "C") (pinfunction "C_C") (pintype "passive"))
    )
    (net (code "83") (name "Net-(R28-Pad1)") (class "Default")
      (node (ref "R28") (pin "1") (pinfunction "1_1") (pintype "passive"))
      (node (ref "TR10") (pin "B") (pinfunction "B_B") (pintype "passive"))
    )
    (net (code "84") (name "Net-(R45-Pad1)") (class "Default")
      (node (ref "R45") (pin "1") (pinfunction "1_1") (pintype "passive"))
      (node (ref "TR12") (pin "B") (pinfunction "B_B") (pintype "passive"))
    )
    (net (code "85") (name "Net-(U2-GP0)") (class "Default")
      (node (ref "U2") (pin "P0") (pinfunction "GP0_P0") (pintype "bidirectional"))
      (node (ref "X3") (pin "2") (pinfunction "S_2") (pintype "passive"))
    )
    (net (code "86") (name "Net-(U2-GP1)") (class "Default")
      (node (ref "U2") (pin "P1") (pinfunction "GP1_P1") (pintype "bidirectional"))
      (node (ref "X3") (pin "3") (pinfunction "S_3") (pintype "passive"))
    )
    (net (code "87") (name "Net-(U2-GP2)") (class "Default")
      (node (ref "U2") (pin "P2") (pinfunction "GP2_P2") (pintype "bidirectional"))
      (node (ref "X3") (pin "4") (pinfunction "S_4") (pintype "passive"))
    )
    (net (code "88") (name "Net-(U2-GP3)") (class "Default")
      (node (ref "U2") (pin "P3") (pinfunction "GP3_P3") (pintype "bidirectional"))
      (node (ref "X3") (pin "5") (pinfunction "S_5") (pintype "passive"))
    )
    (net (code "89") (name "Net-(U2-GP10)") (class "Default")
      (node (ref "R28") (pin "2") (pinfunction "2_2") (pintype "passive"))
      (node (ref "U2") (pin "P10") (pinfunction "GP10_P10") (pintype "bidirectional"))
    )
    (net (code "90") (name "Net-(U2-GP11)") (class "Default")
      (node (ref "R46") (pin "2") (pinfunction "2_2") (pintype "passive"))
      (node (ref "TR12") (pin "E") (pinfunction "E_E") (pintype "passive"))
      (node (ref "U2") (pin "P11") (pinfunction "GP11_P11") (pintype "bidirectional"))
    )
    (net (code "91") (name "Net-(U2-GP12)") (class "Default")
      (node (ref "R9") (pin "2") (pinfunction "2_2") (pintype "passive"))
      (node (ref "U2") (pin "P12") (pinfunction "GP12_P12") (pintype "bidirectional"))
      (node (ref "X1") (pin "4") (pinfunction "1_4") (pintype "passive"))
    )
    (net (code "92") (name "Net-(U2-GP13)") (class "Default")
      (node (ref "R18") (pin "1") (pinfunction "1_1") (pintype "passive"))
      (node (ref "U2") (pin "P13") (pinfunction "GP13_P13") (pintype "bidirectional"))
    )
    (net (code "93") (name "Net-(X1F-1)") (class "Default")
      (node (ref "Q10") (pin "E") (pinfunction "E_E") (pintype "passive"))
      (node (ref "X1") (pin "6") (pinfunction "1_6") (pintype "passive"))
    )
    (net (code "94") (name "Net-(X1G-1)") (class "Default")
      (node (ref "R45") (pin "2") (pinfunction "2_2") (pintype "passive"))
      (node (ref "X1") (pin "7") (pinfunction "1_7") (pintype "passive"))
    )
    (net (code "95") (name "Net-(X8A-S)") (class "Default")
      (node (ref "C11") (pin "+") (pinfunction "+_+") (pintype "passive"))
      (node (ref "L2") (pin "1") (pinfunction "1_1") (pintype "passive"))
      (node (ref "R43") (pin "1") (pinfunction "1_1") (pintype "passive"))
      (node (ref "X8") (pin "1") (pinfunction "S_1") (pintype "passive"))
    )
    (net (code "96") (name "Net-(XDCB-1)") (class "Default")
      (node (ref "D1") (pin "A") (pinfunction "A_A") (pintype "passive"))
      (node (ref "J3") (pin "3") (pinfunction "3_3") (pintype "passive"))
      (node (ref "XDC") (pin "2") (pinfunction "1_2") (pintype "passive"))
    )
    (net (code "97") (name "SH_CP") (class "Default")
      (node (ref "IC1") (pin "11") (pinfunction "SH_CK_11") (pintype "input"))
      (node (ref "IC2") (pin "11") (pinfunction "SH_CK_11") (pintype "input"))
      (node (ref "U2") (pin "P26") (pinfunction "GP26_P26") (pintype "bidirectional"))
    )
    (net (code "98") (name "ST_CP") (class "Default")
      (node (ref "IC1") (pin "12") (pinfunction "ST_CK_12") (pintype "input"))
      (node (ref "IC2") (pin "12") (pinfunction "ST_CK_12") (pintype "input"))
      (node (ref "U2") (pin "P15") (pinfunction "GP15_P15") (pintype "bidirectional"))
    )
    (net (code "99") (name "VCC") (class "Default")
      (node (ref "C1") (pin "+") (pinfunction "+_+") (pintype "passive"))
      (node (ref "Q10") (pin "C") (pinfunction "C_C") (pintype "passive"))
      (node (ref "R16") (pin "1") (pinfunction "1_1") (pintype "passive"))
      (node (ref "R44") (pin "2") (pinfunction "2_2") (pintype "passive"))
      (node (ref "R48") (pin "2") (pinfunction "2_2") (pintype "passive"))
    )
    (net (code "100") (name "unconnected-(IC1A-Q7'-Pad9)") (class "Default")
      (node (ref "IC1") (pin "9") (pinfunction "Q7'_9") (pintype "tri_state"))
    )
    (net (code "101") (name "unconnected-(IC3-CD+-Pad10)") (class "Default")
      (node (ref "IC3") (pin "10") (pinfunction "CD+_10") (pintype "passive"))
    )
    (net (code "102") (name "unconnected-(J3-Pad2)") (class "Default")
      (node (ref "J3") (pin "2") (pinfunction "2_2") (pintype "passive"))
    )
    (net (code "103") (name "unconnected-(U2-GP6-PadP6)") (class "Default")
      (node (ref "U2") (pin "P6") (pinfunction "GP6_P6") (pintype "bidirectional"))
    )
    (net (code "104") (name "unconnected-(U2-GP17-PadP17)") (class "Default")
      (node (ref "U2") (pin "P17") (pinfunction "GP17_P17") (pintype "bidirectional"))
    )
    (net (code "105") (name "unconnected-(U2-GP18-PadP18)") (class "Default")
      (node (ref "U2") (pin "P18") (pinfunction "GP18_P18") (pintype "bidirectional"))
    )
    (net (code "106") (name "unconnected-(U2-GP19-PadP19)") (class "Default")
      (node (ref "U2") (pin "P19") (pinfunction "GP19_P19") (pintype "bidirectional"))
    )
    (net (code "107") (name "unconnected-(U2-GP20-PadP20)") (class "Default")
      (node (ref "U2") (pin "P20") (pinfunction "GP20_P20") (pintype "bidirectional"))
    )
    (net (code "108") (name "unconnected-(U2-GP21-PadP21)") (class "Default")
      (node (ref "U2") (pin "P21") (pinfunction "GP21_P21") (pintype "bidirectional"))
    )
    (net (code "109") (name "unconnected-(U2-GP22-PadP22)") (class "Default")
      (node (ref "U2") (pin "P22") (pinfunction "GP22_P22") (pintype "bidirectional"))
    )
    (net (code "110") (name "unconnected-(U2-GP25-PadP25)") (class "Default")
      (node (ref "U2") (pin "P25") (pinfunction "GP25_P25") (pintype "bidirectional"))
    )
    (net (code "111") (name "unconnected-(U2-GP29-PadP29)") (class "Default")
      (node (ref "U2") (pin "P29") (pinfunction "GP29_P29") (pintype "bidirectional"))
    )
  )
)
